# Relay_Card.net
KiCad netlist of a schematic drawn in EAGLE
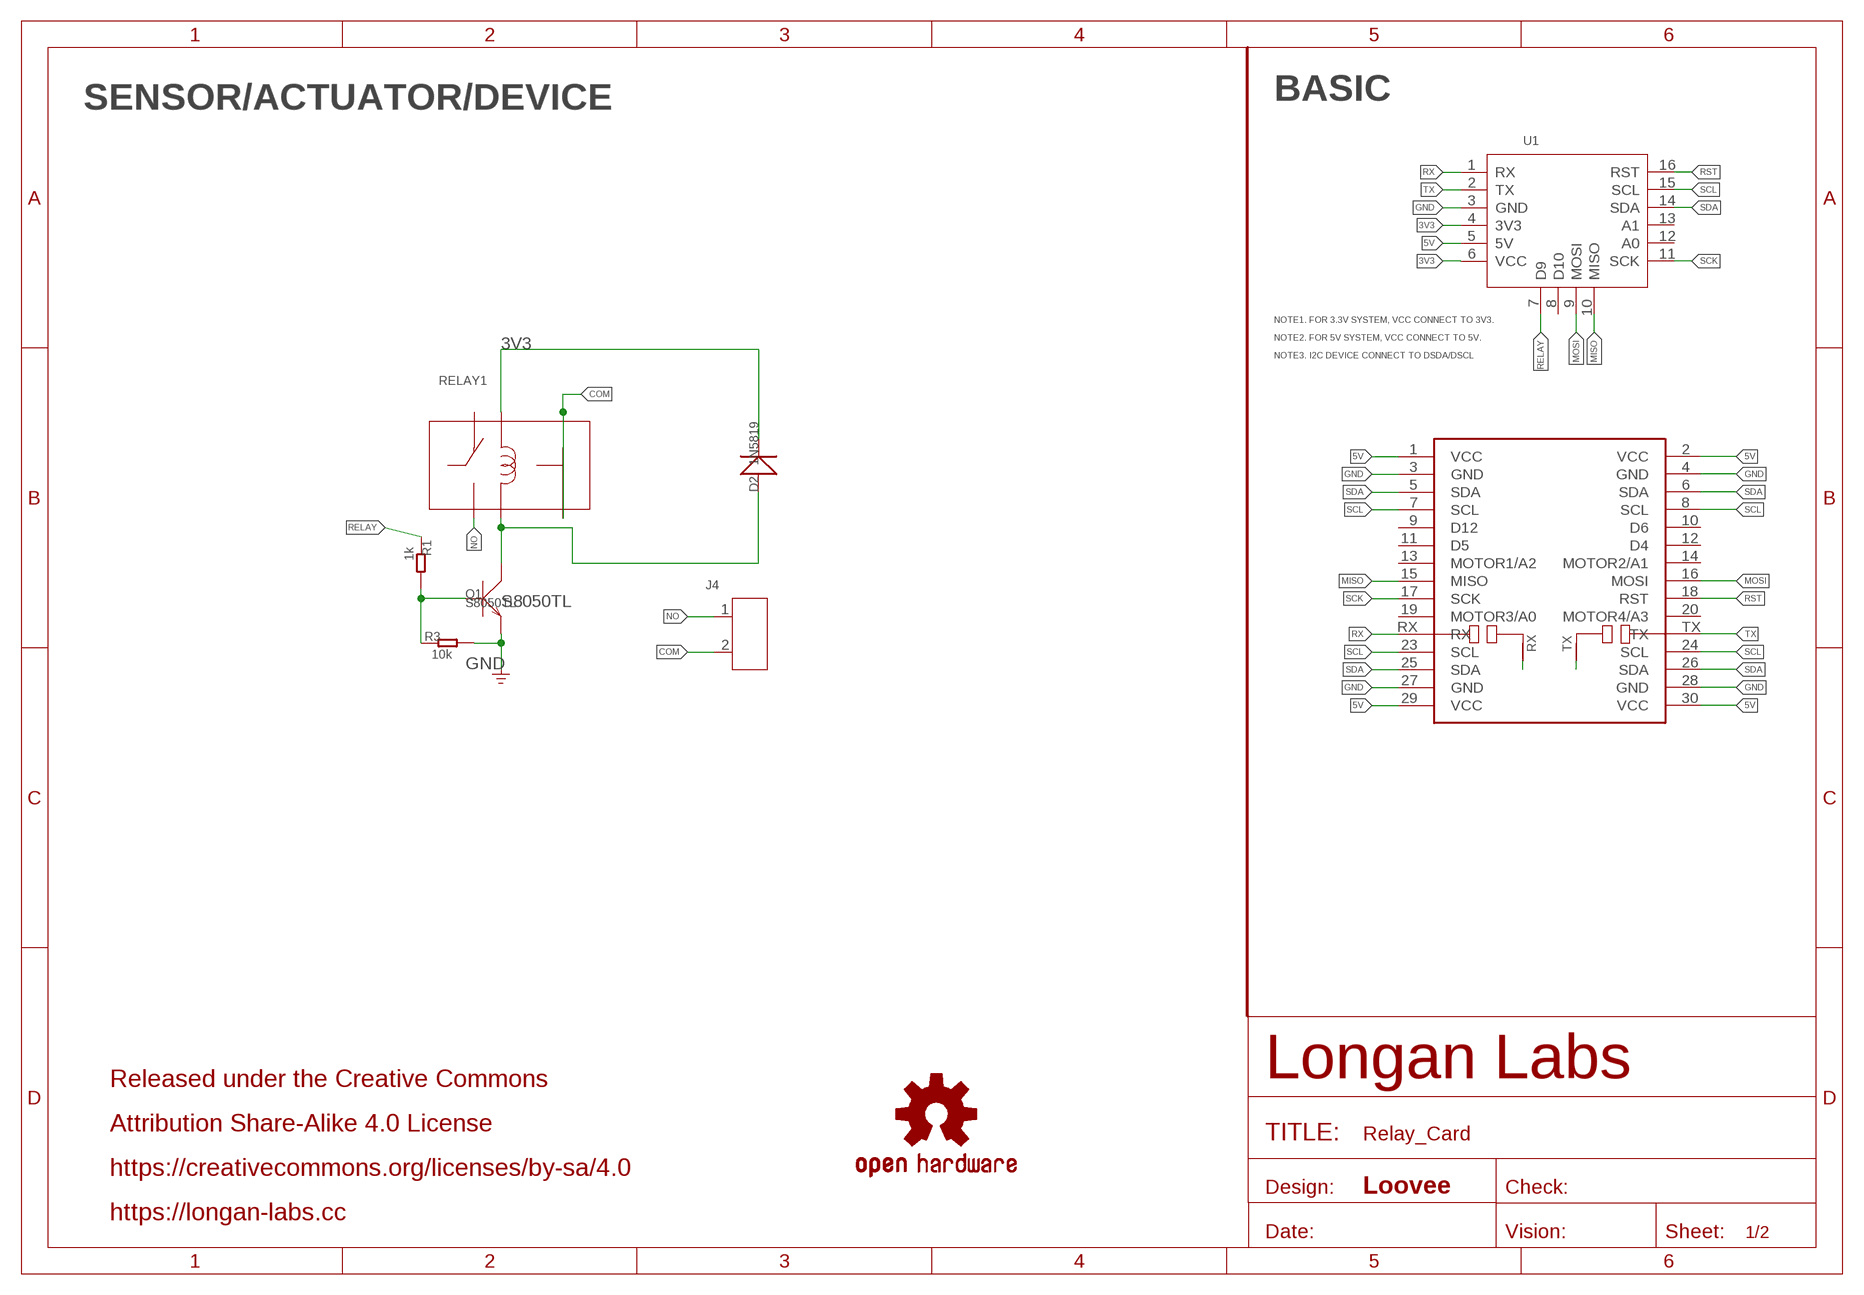
[diagram p0: schematic, sheet 1]

(export (version "E")
  (design (tool "Eeschema 10.0.6"))
  (components
    (comp (ref "D2")
      (value "1N5819")
      (footprint "eagle-import:D2010")
      (libsource (lib "eagle-import") (part "D'DO-214AC'"))
    )
    (comp (ref "J4")
      (value "SCREW-TERMINAL-2P'3.5'")
      (footprint "eagle-import:H2-3.5-7.0X7.0MM")
      (libsource (lib "eagle-import") (part "SCREW-TERMINAL-2P'3.5'"))
    )
    (comp (ref "LOGO2")
      (value "OSHW-LOGOS")
      (footprint "eagle-import:OSHW-LOGO-S")
      (libsource (lib "eagle-import") (part "OSHW-LOGOS"))
    )
    (comp (ref "MOUDLE2")
      (value "MOUDLE-CARDS-UART'BOARD'")
      (footprint "eagle-import:MOUDLE-2X15P-UART")
      (libsource (lib "eagle-import") (part "MOUDLE-CARDS-UART'BOARD'"))
    )
    (comp (ref "Q1")
      (value "S8050TL")
      (footprint "eagle-import:SOT23")
      (libsource (lib "eagle-import") (part "TRANSISTOR-NPN-SOT23"))
    )
    (comp (ref "R1")
      (value "1k")
      (footprint "eagle-import:R0603")
      (libsource (lib "eagle-import") (part "R-0603"))
    )
    (comp (ref "R3")
      (value "10k")
      (footprint "eagle-import:R0603")
      (libsource (lib "eagle-import") (part "R-0603"))
    )
    (comp (ref "RELAY1")
      (value "RELAY-HK4100F")
      (footprint "eagle-import:6P-15.5X10.5X11.8MM")
      (libsource (lib "eagle-import") (part "RELAY-HK4100F"))
    )
    (comp (ref "U1")
      (value "MOUDLE-CARDS")
      (footprint "eagle-import:16P-2.0-CARDS")
      (libsource (lib "eagle-import") (part "MOUDLE-CARDS"))
    )
  )
  (nets
    (net (code "1") (name "3V3") (class "Default")
      (node (ref "D2") (pin "-") (pinfunction "-_-") (pintype "passive"))
      (node (ref "RELAY1") (pin "2") (pinfunction "P$2_2") (pintype "bidirectional"))
      (node (ref "U1") (pin "4") (pinfunction "3V3_4") (pintype "bidirectional"))
      (node (ref "U1") (pin "6") (pinfunction "VCC_6") (pintype "bidirectional"))
    )
    (net (code "2") (name "5V") (class "Default")
      (node (ref "MOUDLE2") (pin "1") (pinfunction "VCC_1") (pintype "bidirectional"))
      (node (ref "MOUDLE2") (pin "2") (pinfunction "VCC_2") (pintype "bidirectional"))
      (node (ref "MOUDLE2") (pin "29") (pinfunction "VCC_29") (pintype "bidirectional"))
      (node (ref "MOUDLE2") (pin "30") (pinfunction "VCC_30") (pintype "bidirectional"))
      (node (ref "U1") (pin "5") (pinfunction "5V_5") (pintype "bidirectional"))
    )
    (net (code "3") (name "COM") (class "Default")
      (node (ref "J4") (pin "2") (pinfunction "2_2") (pintype "bidirectional"))
      (node (ref "RELAY1") (pin "3") (pinfunction "P$3_3") (pintype "bidirectional"))
      (node (ref "RELAY1") (pin "6") (pinfunction "P$6_6") (pintype "bidirectional"))
    )
    (net (code "4") (name "GND") (class "Default")
      (node (ref "MOUDLE2") (pin "27") (pinfunction "GND_27") (pintype "bidirectional"))
      (node (ref "MOUDLE2") (pin "28") (pinfunction "GND_28") (pintype "bidirectional"))
      (node (ref "MOUDLE2") (pin "3") (pinfunction "GND_3") (pintype "bidirectional"))
      (node (ref "MOUDLE2") (pin "4") (pinfunction "GND_4") (pintype "bidirectional"))
      (node (ref "Q1") (pin "2") (pinfunction "E_2") (pintype "passive"))
      (node (ref "R3") (pin "2") (pinfunction "2_2") (pintype "passive"))
      (node (ref "U1") (pin "3") (pinfunction "GND_3") (pintype "bidirectional"))
    )
    (net (code "5") (name "MISO") (class "Default")
      (node (ref "MOUDLE2") (pin "15") (pinfunction "MISO_15") (pintype "bidirectional"))
      (node (ref "U1") (pin "10") (pinfunction "MISO_10") (pintype "bidirectional"))
    )
    (net (code "6") (name "MOSI") (class "Default")
      (node (ref "MOUDLE2") (pin "16") (pinfunction "MOSI_16") (pintype "bidirectional"))
      (node (ref "U1") (pin "9") (pinfunction "MOSI_9") (pintype "bidirectional"))
    )
    (net (code "7") (name "NO") (class "Default")
      (node (ref "J4") (pin "1") (pinfunction "1_1") (pintype "bidirectional"))
      (node (ref "RELAY1") (pin "4") (pinfunction "P$4_4") (pintype "bidirectional"))
    )
    (net (code "8") (name "Net-(MOUDLE2-RX{slash}N-PadRX{slash}N1)") (class "Default")
      (node (ref "MOUDLE2") (pin "RX/N1") (pinfunction "RX/N_RX/N1") (pintype "bidirectional"))
      (node (ref "MOUDLE2") (pin "RX/N2") (pinfunction "RX/N_RX/N2") (pintype "bidirectional"))
    )
    (net (code "9") (name "Net-(MOUDLE2-TX{slash}N-PadTX{slash}N1)") (class "Default")
      (node (ref "MOUDLE2") (pin "TX/N1") (pinfunction "TX/N_TX/N1") (pintype "bidirectional"))
      (node (ref "MOUDLE2") (pin "TX/N2") (pinfunction "TX/N_TX/N2") (pintype "bidirectional"))
    )
    (net (code "10") (name "Net-(Q1-B)") (class "Default")
      (node (ref "Q1") (pin "1") (pinfunction "B_1") (pintype "passive"))
      (node (ref "R1") (pin "2") (pinfunction "2_2") (pintype "passive"))
      (node (ref "R3") (pin "1") (pinfunction "1_1") (pintype "passive"))
    )
    (net (code "11") (name "Net-(Q1-C)") (class "Default")
      (node (ref "D2") (pin "+") (pinfunction "+_+") (pintype "passive"))
      (node (ref "Q1") (pin "3") (pinfunction "C_3") (pintype "passive"))
      (node (ref "RELAY1") (pin "5") (pinfunction "P$5_5") (pintype "bidirectional"))
    )
    (net (code "12") (name "RELAY") (class "Default")
      (node (ref "R1") (pin "1") (pinfunction "1_1") (pintype "passive"))
      (node (ref "U1") (pin "7") (pinfunction "D9_7") (pintype "bidirectional"))
    )
    (net (code "13") (name "RST") (class "Default")
      (node (ref "MOUDLE2") (pin "18") (pinfunction "RST_18") (pintype "bidirectional"))
      (node (ref "U1") (pin "16") (pinfunction "RST_16") (pintype "bidirectional"))
    )
    (net (code "14") (name "RX") (class "Default")
      (node (ref "MOUDLE2") (pin "RX") (pinfunction "RX_RX") (pintype "bidirectional"))
      (node (ref "U1") (pin "1") (pinfunction "RX_1") (pintype "bidirectional"))
    )
    (net (code "15") (name "SCK") (class "Default")
      (node (ref "MOUDLE2") (pin "17") (pinfunction "SCK_17") (pintype "bidirectional"))
      (node (ref "U1") (pin "11") (pinfunction "SCK_11") (pintype "bidirectional"))
    )
    (net (code "16") (name "SCL") (class "Default")
      (node (ref "MOUDLE2") (pin "23") (pinfunction "SCL_23") (pintype "bidirectional"))
      (node (ref "MOUDLE2") (pin "24") (pinfunction "SCL_24") (pintype "bidirectional"))
      (node (ref "MOUDLE2") (pin "7") (pinfunction "SCL_7") (pintype "bidirectional"))
      (node (ref "MOUDLE2") (pin "8") (pinfunction "SCL_8") (pintype "bidirectional"))
      (node (ref "U1") (pin "15") (pinfunction "SCL_15") (pintype "bidirectional"))
    )
    (net (code "17") (name "SDA") (class "Default")
      (node (ref "MOUDLE2") (pin "25") (pinfunction "SDA_25") (pintype "bidirectional"))
      (node (ref "MOUDLE2") (pin "26") (pinfunction "SDA_26") (pintype "bidirectional"))
      (node (ref "MOUDLE2") (pin "5") (pinfunction "SDA_5") (pintype "bidirectional"))
      (node (ref "MOUDLE2") (pin "6") (pinfunction "SDA_6") (pintype "bidirectional"))
      (node (ref "U1") (pin "14") (pinfunction "SDA_14") (pintype "bidirectional"))
    )
    (net (code "18") (name "TX") (class "Default")
      (node (ref "MOUDLE2") (pin "TX") (pinfunction "TX_TX") (pintype "bidirectional"))
      (node (ref "U1") (pin "2") (pinfunction "TX_2") (pintype "bidirectional"))
    )
    (net (code "19") (name "unconnected-(MOUDLE2-D4-Pad12)") (class "Default")
      (node (ref "MOUDLE2") (pin "12") (pinfunction "D4_12") (pintype "bidirectional"))
    )
    (net (code "20") (name "unconnected-(MOUDLE2-D5-Pad11)") (class "Default")
      (node (ref "MOUDLE2") (pin "11") (pinfunction "D5_11") (pintype "bidirectional"))
    )
    (net (code "21") (name "unconnected-(MOUDLE2-D6-Pad10)") (class "Default")
      (node (ref "MOUDLE2") (pin "10") (pinfunction "D6_10") (pintype "bidirectional"))
    )
    (net (code "22") (name "unconnected-(MOUDLE2-D12-Pad9)") (class "Default")
      (node (ref "MOUDLE2") (pin "9") (pinfunction "D12_9") (pintype "bidirectional"))
    )
    (net (code "23") (name "unconnected-(MOUDLE2-MOTOR1{slash}A2-Pad13)") (class "Default")
      (node (ref "MOUDLE2") (pin "13") (pinfunction "MOTOR1/A2_13") (pintype "bidirectional"))
    )
    (net (code "24") (name "unconnected-(MOUDLE2-MOTOR2{slash}A1-Pad14)") (class "Default")
      (node (ref "MOUDLE2") (pin "14") (pinfunction "MOTOR2/A1_14") (pintype "bidirectional"))
    )
    (net (code "25") (name "unconnected-(MOUDLE2-MOTOR3{slash}A0-Pad19)") (class "Default")
      (node (ref "MOUDLE2") (pin "19") (pinfunction "MOTOR3/A0_19") (pintype "bidirectional"))
    )
    (net (code "26") (name "unconnected-(MOUDLE2-MOTOR4{slash}A3-Pad20)") (class "Default")
      (node (ref "MOUDLE2") (pin "20") (pinfunction "MOTOR4/A3_20") (pintype "bidirectional"))
    )
    (net (code "27") (name "unconnected-(RELAY1-P$1-Pad1)") (class "Default")
      (node (ref "RELAY1") (pin "1") (pinfunction "P$1_1") (pintype "bidirectional"))
    )
    (net (code "28") (name "unconnected-(U1-A0-Pad12)") (class "Default")
      (node (ref "U1") (pin "12") (pinfunction "A0_12") (pintype "bidirectional"))
    )
    (net (code "29") (name "unconnected-(U1-A1-Pad13)") (class "Default")
      (node (ref "U1") (pin "13") (pinfunction "A1_13") (pintype "bidirectional"))
    )
    (net (code "30") (name "unconnected-(U1-D10-Pad8)") (class "Default")
      (node (ref "U1") (pin "8") (pinfunction "D10_8") (pintype "bidirectional"))
    )
  )
)
